# SoupPico.net
KiCad netlist of a schematic drawn in EasyEDA Pro
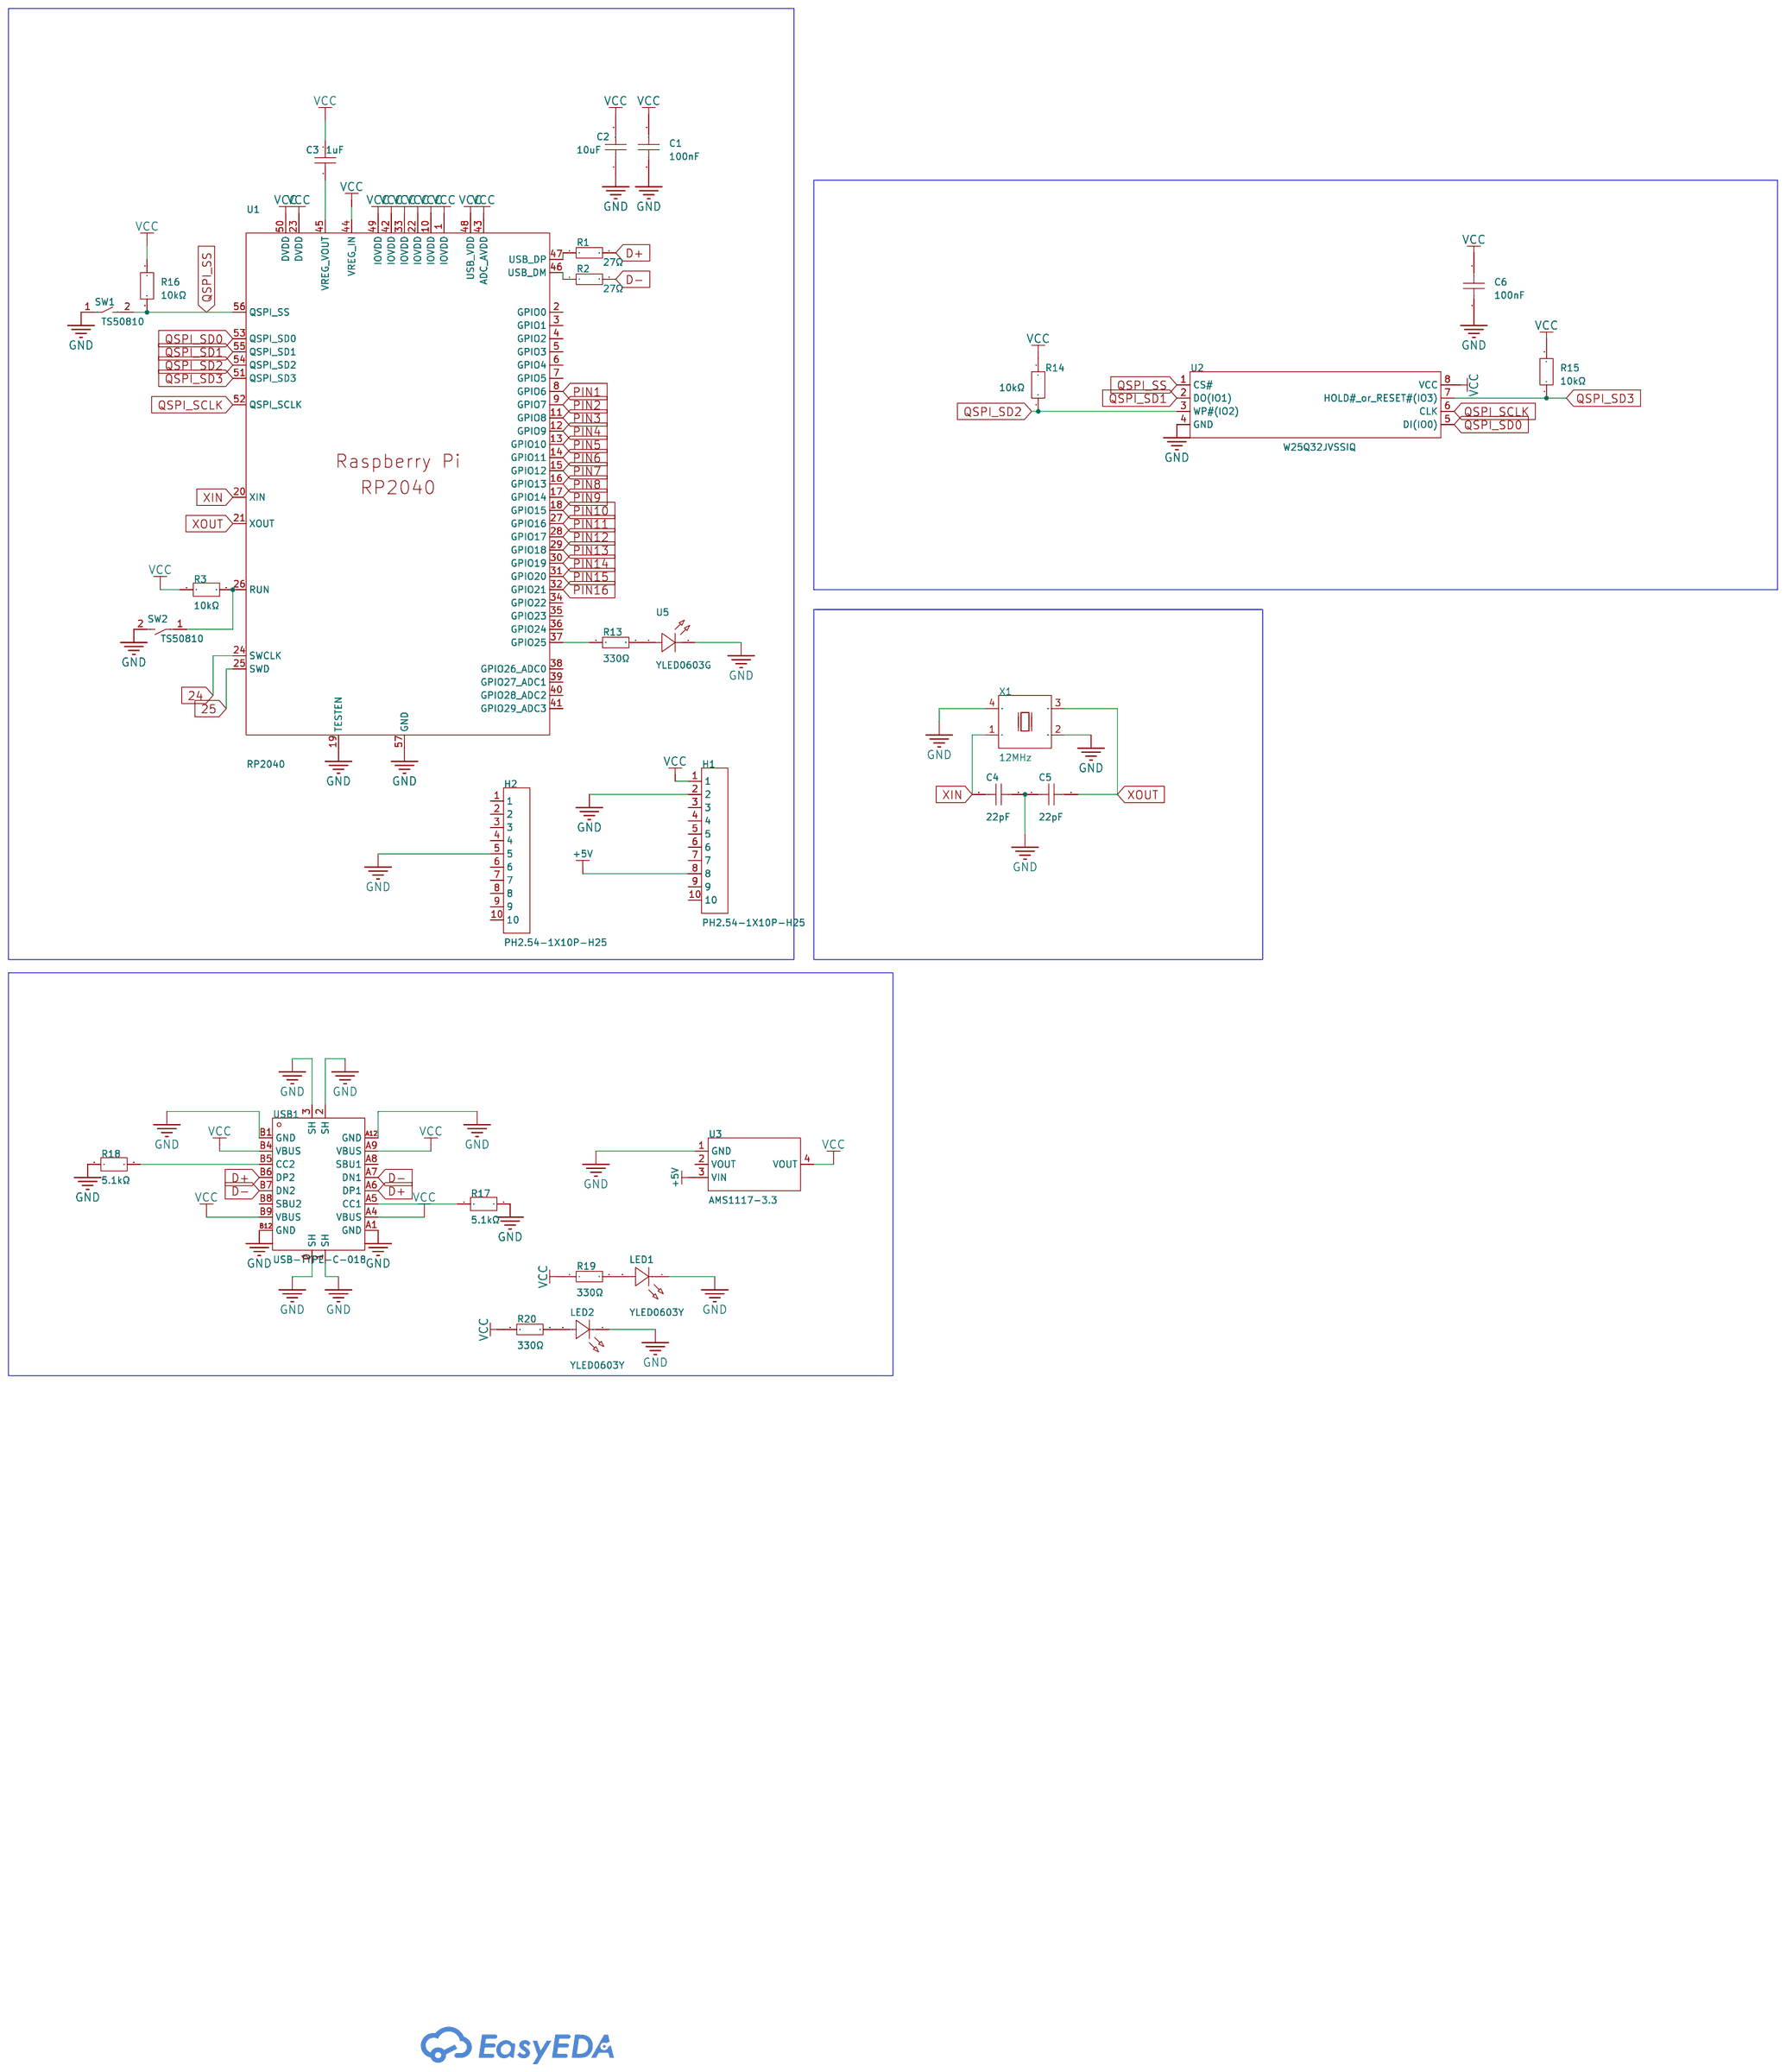
[diagram p0: schematic sheet]

(export (version "E")
  (design (tool "Eeschema 10.0.6"))
  (components
    (comp (ref "C1")
      (value "100nF")
      (footprint "easyedapro:C0603")
      (description "Capacitance:100nF Tolerance:±10% Tolerance:±10% Voltage Rating:50V Temperature Coefficient:X7R")
      (fields
        (field (name "Manufacturer Part") "CC0603KRX7R9BB104")
        (field (name "Manufacturer") "YAGEO(国巨)")
      )
      (libsource (lib "easyedapro") (part "CC0603KRX7R9BB104"))
    )
    (comp (ref "C2")
      (value "10uF")
      (footprint "easyedapro:C0603")
      (description "Capacitance:10uF Tolerance:±10% Tolerance:±10% Voltage Rating:10V Temperature Coefficient:X5R")
      (fields
        (field (name "Manufacturer Part") "CL10A106KP8NNNC")
        (field (name "Manufacturer") "SAMSUNG(三星)")
      )
      (libsource (lib "easyedapro") (part "CL10A106KP8NNNC"))
    )
    (comp (ref "C3")
      (value "1uF")
      (footprint "easyedapro:C0603")
      (description "Capacitance:1uF Tolerance:±10% Tolerance:±10% Voltage Rating:25V Temperature Coefficient:X7R")
      (fields
        (field (name "Manufacturer Part") "CL10B105KA8NNNC")
        (field (name "Manufacturer") "SAMSUNG(三星)")
      )
      (libsource (lib "easyedapro") (part "CL10B105KA8NNNC"))
    )
    (comp (ref "C4")
      (value "22pF")
      (footprint "easyedapro:C0805")
      (description "Capacitance:22pF Tolerance:±5% Tolerance:±5% Voltage Rating:50V Temperature Coefficient:C0G")
      (fields
        (field (name "Manufacturer Part") "TCC0805COG220J500BT")
        (field (name "Manufacturer") "CCTC(三环)")
      )
      (libsource (lib "easyedapro") (part "TCC0805COG220J500BT"))
    )
    (comp (ref "C5")
      (value "22pF")
      (footprint "easyedapro:C0805")
      (description "Capacitance:22pF Tolerance:±5% Tolerance:±5% Voltage Rating:50V Temperature Coefficient:C0G")
      (fields
        (field (name "Manufacturer Part") "TCC0805COG220J500BT")
        (field (name "Manufacturer") "CCTC(三环)")
      )
      (libsource (lib "easyedapro") (part "TCC0805COG220J500BT"))
    )
    (comp (ref "C6")
      (value "100nF")
      (footprint "easyedapro:C0603")
      (description "Capacitance:100nF Tolerance:±10% Tolerance:±10% Voltage Rating:50V Temperature Coefficient:X7R")
      (fields
        (field (name "Manufacturer Part") "CC0603KRX7R9BB104")
        (field (name "Manufacturer") "YAGEO(国巨)")
      )
      (libsource (lib "easyedapro") (part "CC0603KRX7R9BB104"))
    )
    (comp (ref "H1")
      (value "PH2.54-1X10P-H25")
      (footprint "easyedapro:HDR-TH_10P-P2.54-V-M")
      (fields (field (name "Manufacturer") "JXTCONN(聚兴泰)"))
      (libsource (lib "easyedapro") (part "PH2.54-1X10P-H25"))
    )
    (comp (ref "H2")
      (value "PH2.54-1X10P-H25")
      (footprint "easyedapro:HDR-TH_10P-P2.54-V-M")
      (fields (field (name "Manufacturer") "JXTCONN(聚兴泰)"))
      (libsource (lib "easyedapro") (part "PH2.54-1X10P-H25"))
    )
    (comp (ref "LED1")
      (value "YLED0603Y")
      (footprint "easyedapro:LED0603-RD-1")
      (fields (field (name "Manufacturer") "YONGYUTAI(永裕泰)"))
      (libsource (lib "easyedapro") (part "YLED0603Y"))
    )
    (comp (ref "LED2")
      (value "YLED0603Y")
      (footprint "easyedapro:LED0603-RD-1")
      (fields (field (name "Manufacturer") "YONGYUTAI(永裕泰)"))
      (libsource (lib "easyedapro") (part "YLED0603Y"))
    )
    (comp (ref "R1")
      (value "27Ω")
      (footprint "easyedapro:R0603")
      (fields (field (name "Manufacturer Part") "RC0603FR-0727RL") (field (name "Manufacturer") "YAGEO(国巨)"))
      (libsource (lib "easyedapro") (part "RC0603FR-0727RL"))
    )
    (comp (ref "R2")
      (value "27Ω")
      (footprint "easyedapro:R0603")
      (fields (field (name "Manufacturer Part") "RC0603FR-0727RL") (field (name "Manufacturer") "YAGEO(国巨)"))
      (libsource (lib "easyedapro") (part "RC0603FR-0727RL"))
    )
    (comp (ref "R3")
      (value "10kΩ")
      (footprint "easyedapro:R0603")
      (fields (field (name "Manufacturer Part") "FRC0603J103 TS") (field (name "Manufacturer") "FOJAN(富捷)"))
      (libsource (lib "easyedapro") (part "FRC0603J103TS"))
    )
    (comp (ref "R13")
      (value "330Ω")
      (footprint "easyedapro:R0603")
      (fields (field (name "Manufacturer Part") "RC0603FR-07330RL") (field (name "Manufacturer") "YAGEO(国巨)"))
      (libsource (lib "easyedapro") (part "RC0603FR-07330RL"))
    )
    (comp (ref "R14")
      (value "10kΩ")
      (footprint "easyedapro:R0603")
      (fields (field (name "Manufacturer Part") "FRC0603J103 TS") (field (name "Manufacturer") "FOJAN(富捷)"))
      (libsource (lib "easyedapro") (part "FRC0603J103TS"))
    )
    (comp (ref "R15")
      (value "10kΩ")
      (footprint "easyedapro:R0603")
      (fields (field (name "Manufacturer Part") "FRC0603J103 TS") (field (name "Manufacturer") "FOJAN(富捷)"))
      (libsource (lib "easyedapro") (part "FRC0603J103TS"))
    )
    (comp (ref "R16")
      (value "10kΩ")
      (footprint "easyedapro:R0603")
      (fields (field (name "Manufacturer Part") "FRC0603J103 TS") (field (name "Manufacturer") "FOJAN(富捷)"))
      (libsource (lib "easyedapro") (part "FRC0603J103TS"))
    )
    (comp (ref "R17")
      (value "5.1kΩ")
      (footprint "easyedapro:R0603")
      (fields (field (name "Manufacturer Part") "FRC0603F5101TS") (field (name "Manufacturer") "FOJAN(富捷)"))
      (libsource (lib "easyedapro") (part "FRC0603F5101TS"))
    )
    (comp (ref "R18")
      (value "5.1kΩ")
      (footprint "easyedapro:R0603")
      (fields (field (name "Manufacturer Part") "FRC0603F5101TS") (field (name "Manufacturer") "FOJAN(富捷)"))
      (libsource (lib "easyedapro") (part "FRC0603F5101TS"))
    )
    (comp (ref "R19")
      (value "330Ω")
      (footprint "easyedapro:R0603")
      (fields (field (name "Manufacturer Part") "RC0603FR-07330RL") (field (name "Manufacturer") "YAGEO(国巨)"))
      (libsource (lib "easyedapro") (part "RC0603FR-07330RL"))
    )
    (comp (ref "R20")
      (value "330Ω")
      (footprint "easyedapro:R0603")
      (fields (field (name "Manufacturer Part") "RC0603FR-07330RL") (field (name "Manufacturer") "YAGEO(国巨)"))
      (libsource (lib "easyedapro") (part "RC0603FR-07330RL"))
    )
    (comp (ref "SW1")
      (value "TS50810")
      (footprint "easyedapro:SW-SMD_L6.2-W3.7-LS8.0")
      (fields (field (name "Manufacturer") "HMTCONN(华明通)"))
      (libsource (lib "easyedapro") (part "TS50810-411-02528"))
    )
    (comp (ref "SW2")
      (value "TS50810")
      (footprint "easyedapro:SW-SMD_L6.2-W3.7-LS8.0")
      (fields (field (name "Manufacturer") "HMTCONN(华明通)"))
      (libsource (lib "easyedapro") (part "TS50810-411-02528"))
    )
    (comp (ref "U1")
      (value "RP2040")
      (footprint "easyedapro:QFN-56_L7.0-W7.0-P0.40-TL-EP4.0")
      (fields (field (name "Manufacturer") "Raspberry Pi(树莓派)"))
      (libsource (lib "easyedapro") (part "RP2040_C2961140"))
    )
    (comp (ref "U2")
      (value "W25Q32JVSSIQ")
      (footprint "easyedapro:SOIC-8_L5.3-W5.3-P1.27-LS8.0-BL")
      (fields (field (name "Manufacturer") "Winbond(华邦)"))
      (libsource (lib "easyedapro") (part "W25Q32JVSSIQ_C179173"))
    )
    (comp (ref "U3")
      (value "AMS1117-3.3")
      (footprint "easyedapro:SOT-223-3_L6.5-W3.4-P2.30-LS7.0-BR")
      (fields (field (name "Manufacturer") "AMS"))
      (libsource (lib "easyedapro") (part "AMS1117-3.3"))
    )
    (comp (ref "U5")
      (value "YLED0603G")
      (footprint "easyedapro:LED0603-FD")
      (fields (field (name "Manufacturer") "YONGYUTAI(永裕泰)"))
      (libsource (lib "easyedapro") (part "YLED0603G"))
    )
    (comp (ref "USB1")
      (value "USB-TYPE-C-018")
      (footprint "easyedapro:USB-C_SMD-TYPE-C-31-M-12")
      (fields (field (name "Manufacturer") "DEALON(德艺隆)"))
      (libsource (lib "easyedapro") (part "USB-TYPE-C-018"))
    )
    (comp (ref "X1")
      (value "12MHz")
      (footprint "easyedapro:OSC-SMD_4P-L5.0-W3.2-BL_SG5032")
      (fields
        (field (name "Manufacturer Part") "OVETGLJANF-12MHZ")
        (field (name "Manufacturer") "TAITIEN(泰艺电子)")
      )
      (libsource (lib "easyedapro") (part "OVETGLJANF-12MHZ"))
    )
  )
  (nets
    (net (code "1") (name "+5V") (class "Default")
      (node (ref "H1") (pin "8") (pinfunction "8_8") (pintype "unspecified"))
      (node (ref "U3") (pin "3") (pinfunction "VIN_3") (pintype "unspecified"))
    )
    (net (code "2") (name "24") (class "Default")
      (node (ref "U1") (pin "24") (pinfunction "SWCLK_24") (pintype "output"))
    )
    (net (code "3") (name "25") (class "Default")
      (node (ref "U1") (pin "25") (pinfunction "SWD_25") (pintype "bidirectional"))
    )
    (net (code "4") (name "D+") (class "Default")
      (node (ref "R1") (pin "2") (pinfunction "2_2") (pintype "input"))
      (node (ref "USB1") (pin "A6") (pinfunction "DP1_A6") (pintype "unspecified"))
      (node (ref "USB1") (pin "B6") (pinfunction "DP2_B6") (pintype "unspecified"))
    )
    (net (code "5") (name "D-") (class "Default")
      (node (ref "R2") (pin "2") (pinfunction "2_2") (pintype "input"))
      (node (ref "USB1") (pin "A7") (pinfunction "DN1_A7") (pintype "unspecified"))
      (node (ref "USB1") (pin "B7") (pinfunction "DN2_B7") (pintype "unspecified"))
    )
    (net (code "6") (name "GND") (class "Default")
      (node (ref "C1") (pin "2") (pinfunction "2_2") (pintype "unspecified"))
      (node (ref "C2") (pin "1") (pinfunction "1_1") (pintype "unspecified"))
      (node (ref "C4") (pin "1") (pinfunction "1_1") (pintype "unspecified"))
      (node (ref "C5") (pin "1") (pinfunction "1_1") (pintype "unspecified"))
      (node (ref "C6") (pin "2") (pinfunction "2_2") (pintype "unspecified"))
      (node (ref "H1") (pin "2") (pinfunction "2_2") (pintype "unspecified"))
      (node (ref "H2") (pin "5") (pinfunction "5_5") (pintype "unspecified"))
      (node (ref "LED1") (pin "1") (pinfunction "C_1") (pintype "unspecified"))
      (node (ref "LED2") (pin "1") (pinfunction "C_1") (pintype "unspecified"))
      (node (ref "R17") (pin "2") (pinfunction "2_2") (pintype "unspecified"))
      (node (ref "R18") (pin "1") (pinfunction "1_1") (pintype "unspecified"))
      (node (ref "SW1") (pin "1") (pinfunction "1_1") (pintype "unspecified"))
      (node (ref "SW2") (pin "2") (pinfunction "2_2") (pintype "unspecified"))
      (node (ref "U1") (pin "19") (pinfunction "TESTEN_19") (pintype "unspecified"))
      (node (ref "U1") (pin "57") (pinfunction "GND_57") (pintype "bidirectional"))
      (node (ref "U2") (pin "4") (pinfunction "GND_4") (pintype "unspecified"))
      (node (ref "U3") (pin "1") (pinfunction "GND_1") (pintype "unspecified"))
      (node (ref "U5") (pin "2") (pinfunction "-_2") (pintype "unspecified"))
      (node (ref "USB1") (pin "0") (pinfunction "SH_0") (pintype "unspecified"))
      (node (ref "USB1") (pin "1") (pinfunction "SH_1") (pintype "unspecified"))
      (node (ref "USB1") (pin "2") (pinfunction "SH_2") (pintype "unspecified"))
      (node (ref "USB1") (pin "3") (pinfunction "SH_3") (pintype "unspecified"))
      (node (ref "USB1") (pin "A1") (pinfunction "GND_A1") (pintype "unspecified"))
      (node (ref "USB1") (pin "A12") (pinfunction "GND_A12") (pintype "unspecified"))
      (node (ref "USB1") (pin "B1") (pinfunction "GND_B1") (pintype "unspecified"))
      (node (ref "USB1") (pin "B12") (pinfunction "GND_B12") (pintype "unspecified"))
      (node (ref "X1") (pin "2") (pinfunction "GND_2") (pintype "unspecified"))
      (node (ref "X1") (pin "4") (pinfunction "VCC_4") (pintype "unspecified"))
    )
    (net (code "7") (name "Net-(LED1-A)") (class "Default")
      (node (ref "LED1") (pin "2") (pinfunction "A_2") (pintype "unspecified"))
      (node (ref "R19") (pin "2") (pinfunction "2_2") (pintype "input"))
    )
    (net (code "8") (name "Net-(LED2-A)") (class "Default")
      (node (ref "LED2") (pin "2") (pinfunction "A_2") (pintype "unspecified"))
      (node (ref "R20") (pin "2") (pinfunction "2_2") (pintype "input"))
    )
    (net (code "9") (name "Net-(U1-GPIO25)") (class "Default")
      (node (ref "R13") (pin "1") (pinfunction "1_1") (pintype "input"))
      (node (ref "U1") (pin "37") (pinfunction "GPIO25_37") (pintype "bidirectional"))
    )
    (net (code "10") (name "Net-(U1-RUN)") (class "Default")
      (node (ref "R3") (pin "2") (pinfunction "2_2") (pintype "unspecified"))
      (node (ref "SW2") (pin "1") (pinfunction "1_1") (pintype "unspecified"))
      (node (ref "U1") (pin "26") (pinfunction "RUN_26") (pintype "input"))
    )
    (net (code "11") (name "Net-(U1-USB_DM)") (class "Default")
      (node (ref "R2") (pin "1") (pinfunction "1_1") (pintype "input"))
      (node (ref "U1") (pin "46") (pinfunction "USB_DM_46") (pintype "bidirectional"))
    )
    (net (code "12") (name "Net-(U1-USB_DP)") (class "Default")
      (node (ref "R1") (pin "1") (pinfunction "1_1") (pintype "input"))
      (node (ref "U1") (pin "47") (pinfunction "USB_DP_47") (pintype "bidirectional"))
    )
    (net (code "13") (name "Net-(U1-VREG_VOUT)") (class "Default")
      (node (ref "C3") (pin "1") (pinfunction "1_1") (pintype "input"))
      (node (ref "U1") (pin "45") (pinfunction "VREG_VOUT_45") (pintype "bidirectional"))
    )
    (net (code "14") (name "Net-(U5-+)") (class "Default")
      (node (ref "R13") (pin "2") (pinfunction "2_2") (pintype "input"))
      (node (ref "U5") (pin "1") (pinfunction "+_1") (pintype "unspecified"))
    )
    (net (code "15") (name "Net-(USB1-CC1)") (class "Default")
      (node (ref "R17") (pin "1") (pinfunction "1_1") (pintype "unspecified"))
      (node (ref "USB1") (pin "A5") (pinfunction "CC1_A5") (pintype "unspecified"))
    )
    (net (code "16") (name "Net-(USB1-CC2)") (class "Default")
      (node (ref "R18") (pin "2") (pinfunction "2_2") (pintype "unspecified"))
      (node (ref "USB1") (pin "B5") (pinfunction "CC2_B5") (pintype "unspecified"))
    )
    (net (code "17") (name "PIN1") (class "Default")
      (node (ref "U1") (pin "8") (pinfunction "GPIO6_8") (pintype "bidirectional"))
    )
    (net (code "18") (name "PIN2") (class "Default")
      (node (ref "U1") (pin "9") (pinfunction "GPIO7_9") (pintype "bidirectional"))
    )
    (net (code "19") (name "PIN3") (class "Default")
      (node (ref "U1") (pin "11") (pinfunction "GPIO8_11") (pintype "bidirectional"))
    )
    (net (code "20") (name "PIN4") (class "Default")
      (node (ref "U1") (pin "12") (pinfunction "GPIO9_12") (pintype "bidirectional"))
    )
    (net (code "21") (name "PIN5") (class "Default")
      (node (ref "U1") (pin "13") (pinfunction "GPIO10_13") (pintype "bidirectional"))
    )
    (net (code "22") (name "PIN6") (class "Default")
      (node (ref "U1") (pin "14") (pinfunction "GPIO11_14") (pintype "bidirectional"))
    )
    (net (code "23") (name "PIN7") (class "Default")
      (node (ref "U1") (pin "15") (pinfunction "GPIO12_15") (pintype "bidirectional"))
    )
    (net (code "24") (name "PIN8") (class "Default")
      (node (ref "U1") (pin "16") (pinfunction "GPIO13_16") (pintype "bidirectional"))
    )
    (net (code "25") (name "PIN9") (class "Default")
      (node (ref "U1") (pin "17") (pinfunction "GPIO14_17") (pintype "bidirectional"))
    )
    (net (code "26") (name "PIN10") (class "Default")
      (node (ref "U1") (pin "18") (pinfunction "GPIO15_18") (pintype "bidirectional"))
    )
    (net (code "27") (name "PIN11") (class "Default")
      (node (ref "U1") (pin "27") (pinfunction "GPIO16_27") (pintype "bidirectional"))
    )
    (net (code "28") (name "PIN12") (class "Default")
      (node (ref "U1") (pin "28") (pinfunction "GPIO17_28") (pintype "bidirectional"))
    )
    (net (code "29") (name "PIN13") (class "Default")
      (node (ref "U1") (pin "29") (pinfunction "GPIO18_29") (pintype "bidirectional"))
    )
    (net (code "30") (name "PIN14") (class "Default")
      (node (ref "U1") (pin "30") (pinfunction "GPIO19_30") (pintype "bidirectional"))
    )
    (net (code "31") (name "PIN15") (class "Default")
      (node (ref "U1") (pin "31") (pinfunction "GPIO20_31") (pintype "bidirectional"))
    )
    (net (code "32") (name "PIN16") (class "Default")
      (node (ref "U1") (pin "32") (pinfunction "GPIO21_32") (pintype "bidirectional"))
    )
    (net (code "33") (name "QSPI_SCLK") (class "Default")
      (node (ref "U1") (pin "52") (pinfunction "QSPI_SCLK_52") (pintype "output"))
      (node (ref "U2") (pin "6") (pinfunction "CLK_6") (pintype "unspecified"))
    )
    (net (code "34") (name "QSPI_SD0") (class "Default")
      (node (ref "U1") (pin "53") (pinfunction "QSPI_SD0_53") (pintype "bidirectional"))
      (node (ref "U2") (pin "5") (pinfunction "DI(IO0)_5") (pintype "unspecified"))
    )
    (net (code "35") (name "QSPI_SD1") (class "Default")
      (node (ref "U1") (pin "55") (pinfunction "QSPI_SD1_55") (pintype "bidirectional"))
      (node (ref "U2") (pin "2") (pinfunction "DO(IO1)_2") (pintype "unspecified"))
    )
    (net (code "36") (name "QSPI_SD2") (class "Default")
      (node (ref "R14") (pin "2") (pinfunction "2_2") (pintype "unspecified"))
      (node (ref "U1") (pin "54") (pinfunction "QSPI_SD2_54") (pintype "bidirectional"))
      (node (ref "U2") (pin "3") (pinfunction "WP#(IO2)_3") (pintype "unspecified"))
    )
    (net (code "37") (name "QSPI_SD3") (class "Default")
      (node (ref "R15") (pin "1") (pinfunction "1_1") (pintype "unspecified"))
      (node (ref "U1") (pin "51") (pinfunction "QSPI_SD3_51") (pintype "bidirectional"))
      (node (ref "U2") (pin "7") (pinfunction "HOLD#_or_RESET#(IO3)_7") (pintype "unspecified"))
    )
    (net (code "38") (name "QSPI_SS") (class "Default")
      (node (ref "R16") (pin "2") (pinfunction "2_2") (pintype "unspecified"))
      (node (ref "SW1") (pin "2") (pinfunction "2_2") (pintype "unspecified"))
      (node (ref "U1") (pin "56") (pinfunction "QSPI_SS_56") (pintype "bidirectional"))
      (node (ref "U2") (pin "1") (pinfunction "CS#_1") (pintype "unspecified"))
    )
    (net (code "39") (name "VCC") (class "Default")
      (node (ref "C1") (pin "1") (pinfunction "1_1") (pintype "unspecified"))
      (node (ref "C2") (pin "2") (pinfunction "2_2") (pintype "unspecified"))
      (node (ref "C3") (pin "2") (pinfunction "2_2") (pintype "input"))
      (node (ref "C6") (pin "1") (pinfunction "1_1") (pintype "unspecified"))
      (node (ref "H1") (pin "1") (pinfunction "1_1") (pintype "unspecified"))
      (node (ref "R14") (pin "1") (pinfunction "1_1") (pintype "unspecified"))
      (node (ref "R15") (pin "2") (pinfunction "2_2") (pintype "unspecified"))
      (node (ref "R16") (pin "1") (pinfunction "1_1") (pintype "unspecified"))
      (node (ref "R19") (pin "1") (pinfunction "1_1") (pintype "input"))
      (node (ref "R20") (pin "1") (pinfunction "1_1") (pintype "input"))
      (node (ref "R3") (pin "1") (pinfunction "1_1") (pintype "unspecified"))
      (node (ref "U1") (pin "1") (pinfunction "IOVDD_1") (pintype "bidirectional"))
      (node (ref "U1") (pin "10") (pinfunction "IOVDD_10") (pintype "bidirectional"))
      (node (ref "U1") (pin "22") (pinfunction "IOVDD_22") (pintype "bidirectional"))
      (node (ref "U1") (pin "23") (pinfunction "DVDD_23") (pintype "bidirectional"))
      (node (ref "U1") (pin "33") (pinfunction "IOVDD_33") (pintype "bidirectional"))
      (node (ref "U1") (pin "42") (pinfunction "IOVDD_42") (pintype "bidirectional"))
      (node (ref "U1") (pin "43") (pinfunction "ADC_AVDD_43") (pintype "bidirectional"))
      (node (ref "U1") (pin "44") (pinfunction "VREG_IN_44") (pintype "bidirectional"))
      (node (ref "U1") (pin "48") (pinfunction "USB_VDD_48") (pintype "bidirectional"))
      (node (ref "U1") (pin "49") (pinfunction "IOVDD_49") (pintype "bidirectional"))
      (node (ref "U1") (pin "50") (pinfunction "DVDD_50") (pintype "bidirectional"))
      (node (ref "U2") (pin "8") (pinfunction "VCC_8") (pintype "unspecified"))
      (node (ref "U3") (pin "4") (pinfunction "VOUT_4") (pintype "unspecified"))
      (node (ref "USB1") (pin "A4") (pinfunction "VBUS_A4") (pintype "unspecified"))
      (node (ref "USB1") (pin "A9") (pinfunction "VBUS_A9") (pintype "unspecified"))
      (node (ref "USB1") (pin "B4") (pinfunction "VBUS_B4") (pintype "unspecified"))
      (node (ref "USB1") (pin "B9") (pinfunction "VBUS_B9") (pintype "unspecified"))
    )
    (net (code "40") (name "XIN") (class "Default")
      (node (ref "C4") (pin "2") (pinfunction "2_2") (pintype "unspecified"))
      (node (ref "U1") (pin "20") (pinfunction "XIN_20") (pintype "input"))
      (node (ref "X1") (pin "1") (pinfunction "tri_1") (pintype "unspecified"))
    )
    (net (code "41") (name "XOUT") (class "Default")
      (node (ref "C5") (pin "2") (pinfunction "2_2") (pintype "unspecified"))
      (node (ref "U1") (pin "21") (pinfunction "XOUT_21") (pintype "unspecified"))
      (node (ref "X1") (pin "3") (pinfunction "OUT_3") (pintype "unspecified"))
    )
    (net (code "42") (name "unconnected-(H1-Pad3)") (class "Default")
      (node (ref "H1") (pin "3") (pinfunction "3_3") (pintype "unspecified"))
    )
    (net (code "43") (name "unconnected-(H1-Pad4)") (class "Default")
      (node (ref "H1") (pin "4") (pinfunction "4_4") (pintype "unspecified"))
    )
    (net (code "44") (name "unconnected-(H1-Pad5)") (class "Default")
      (node (ref "H1") (pin "5") (pinfunction "5_5") (pintype "unspecified"))
    )
    (net (code "45") (name "unconnected-(H1-Pad6)") (class "Default")
      (node (ref "H1") (pin "6") (pinfunction "6_6") (pintype "unspecified"))
    )
    (net (code "46") (name "unconnected-(H1-Pad7)") (class "Default")
      (node (ref "H1") (pin "7") (pinfunction "7_7") (pintype "unspecified"))
    )
    (net (code "47") (name "unconnected-(H1-Pad9)") (class "Default")
      (node (ref "H1") (pin "9") (pinfunction "9_9") (pintype "unspecified"))
    )
    (net (code "48") (name "unconnected-(H1-Pad10)") (class "Default")
      (node (ref "H1") (pin "10") (pinfunction "10_10") (pintype "unspecified"))
    )
    (net (code "49") (name "unconnected-(H2-Pad1)") (class "Default")
      (node (ref "H2") (pin "1") (pinfunction "1_1") (pintype "unspecified"))
    )
    (net (code "50") (name "unconnected-(H2-Pad2)") (class "Default")
      (node (ref "H2") (pin "2") (pinfunction "2_2") (pintype "unspecified"))
    )
    (net (code "51") (name "unconnected-(H2-Pad3)") (class "Default")
      (node (ref "H2") (pin "3") (pinfunction "3_3") (pintype "unspecified"))
    )
    (net (code "52") (name "unconnected-(H2-Pad4)") (class "Default")
      (node (ref "H2") (pin "4") (pinfunction "4_4") (pintype "unspecified"))
    )
    (net (code "53") (name "unconnected-(H2-Pad6)") (class "Default")
      (node (ref "H2") (pin "6") (pinfunction "6_6") (pintype "unspecified"))
    )
    (net (code "54") (name "unconnected-(H2-Pad7)") (class "Default")
      (node (ref "H2") (pin "7") (pinfunction "7_7") (pintype "unspecified"))
    )
    (net (code "55") (name "unconnected-(H2-Pad8)") (class "Default")
      (node (ref "H2") (pin "8") (pinfunction "8_8") (pintype "unspecified"))
    )
    (net (code "56") (name "unconnected-(H2-Pad9)") (class "Default")
      (node (ref "H2") (pin "9") (pinfunction "9_9") (pintype "unspecified"))
    )
    (net (code "57") (name "unconnected-(H2-Pad10)") (class "Default")
      (node (ref "H2") (pin "10") (pinfunction "10_10") (pintype "unspecified"))
    )
    (net (code "58") (name "unconnected-(U1-GPIO0-Pad2)") (class "Default")
      (node (ref "U1") (pin "2") (pinfunction "GPIO0_2") (pintype "bidirectional"))
    )
    (net (code "59") (name "unconnected-(U1-GPIO1-Pad3)") (class "Default")
      (node (ref "U1") (pin "3") (pinfunction "GPIO1_3") (pintype "bidirectional"))
    )
    (net (code "60") (name "unconnected-(U1-GPIO2-Pad4)") (class "Default")
      (node (ref "U1") (pin "4") (pinfunction "GPIO2_4") (pintype "bidirectional"))
    )
    (net (code "61") (name "unconnected-(U1-GPIO3-Pad5)") (class "Default")
      (node (ref "U1") (pin "5") (pinfunction "GPIO3_5") (pintype "bidirectional"))
    )
    (net (code "62") (name "unconnected-(U1-GPIO4-Pad6)") (class "Default")
      (node (ref "U1") (pin "6") (pinfunction "GPIO4_6") (pintype "bidirectional"))
    )
    (net (code "63") (name "unconnected-(U1-GPIO5-Pad7)") (class "Default")
      (node (ref "U1") (pin "7") (pinfunction "GPIO5_7") (pintype "bidirectional"))
    )
    (net (code "64") (name "unconnected-(U1-GPIO22-Pad34)") (class "Default")
      (node (ref "U1") (pin "34") (pinfunction "GPIO22_34") (pintype "bidirectional"))
    )
    (net (code "65") (name "unconnected-(U1-GPIO23-Pad35)") (class "Default")
      (node (ref "U1") (pin "35") (pinfunction "GPIO23_35") (pintype "bidirectional"))
    )
    (net (code "66") (name "unconnected-(U1-GPIO24-Pad36)") (class "Default")
      (node (ref "U1") (pin "36") (pinfunction "GPIO24_36") (pintype "bidirectional"))
    )
    (net (code "67") (name "unconnected-(U1-GPIO26_ADC0-Pad38)") (class "Default")
      (node (ref "U1") (pin "38") (pinfunction "GPIO26_ADC0_38") (pintype "bidirectional"))
    )
    (net (code "68") (name "unconnected-(U1-GPIO27_ADC1-Pad39)") (class "Default")
      (node (ref "U1") (pin "39") (pinfunction "GPIO27_ADC1_39") (pintype "bidirectional"))
    )
    (net (code "69") (name "unconnected-(U1-GPIO28_ADC2-Pad40)") (class "Default")
      (node (ref "U1") (pin "40") (pinfunction "GPIO28_ADC2_40") (pintype "bidirectional"))
    )
    (net (code "70") (name "unconnected-(U1-GPIO29_ADC3-Pad41)") (class "Default")
      (node (ref "U1") (pin "41") (pinfunction "GPIO29_ADC3_41") (pintype "bidirectional"))
    )
    (net (code "71") (name "unconnected-(U3-VOUT-Pad2)") (class "Default")
      (node (ref "U3") (pin "2") (pinfunction "VOUT_2") (pintype "unspecified"))
    )
    (net (code "72") (name "unconnected-(USB1-SBU1-PadA8)") (class "Default")
      (node (ref "USB1") (pin "A8") (pinfunction "SBU1_A8") (pintype "unspecified"))
    )
    (net (code "73") (name "unconnected-(USB1-SBU2-PadB8)") (class "Default")
      (node (ref "USB1") (pin "B8") (pinfunction "SBU2_B8") (pintype "unspecified"))
    )
  )
)
